# DI_DO.net
KiCad netlist of a schematic drawn in Altium Designer
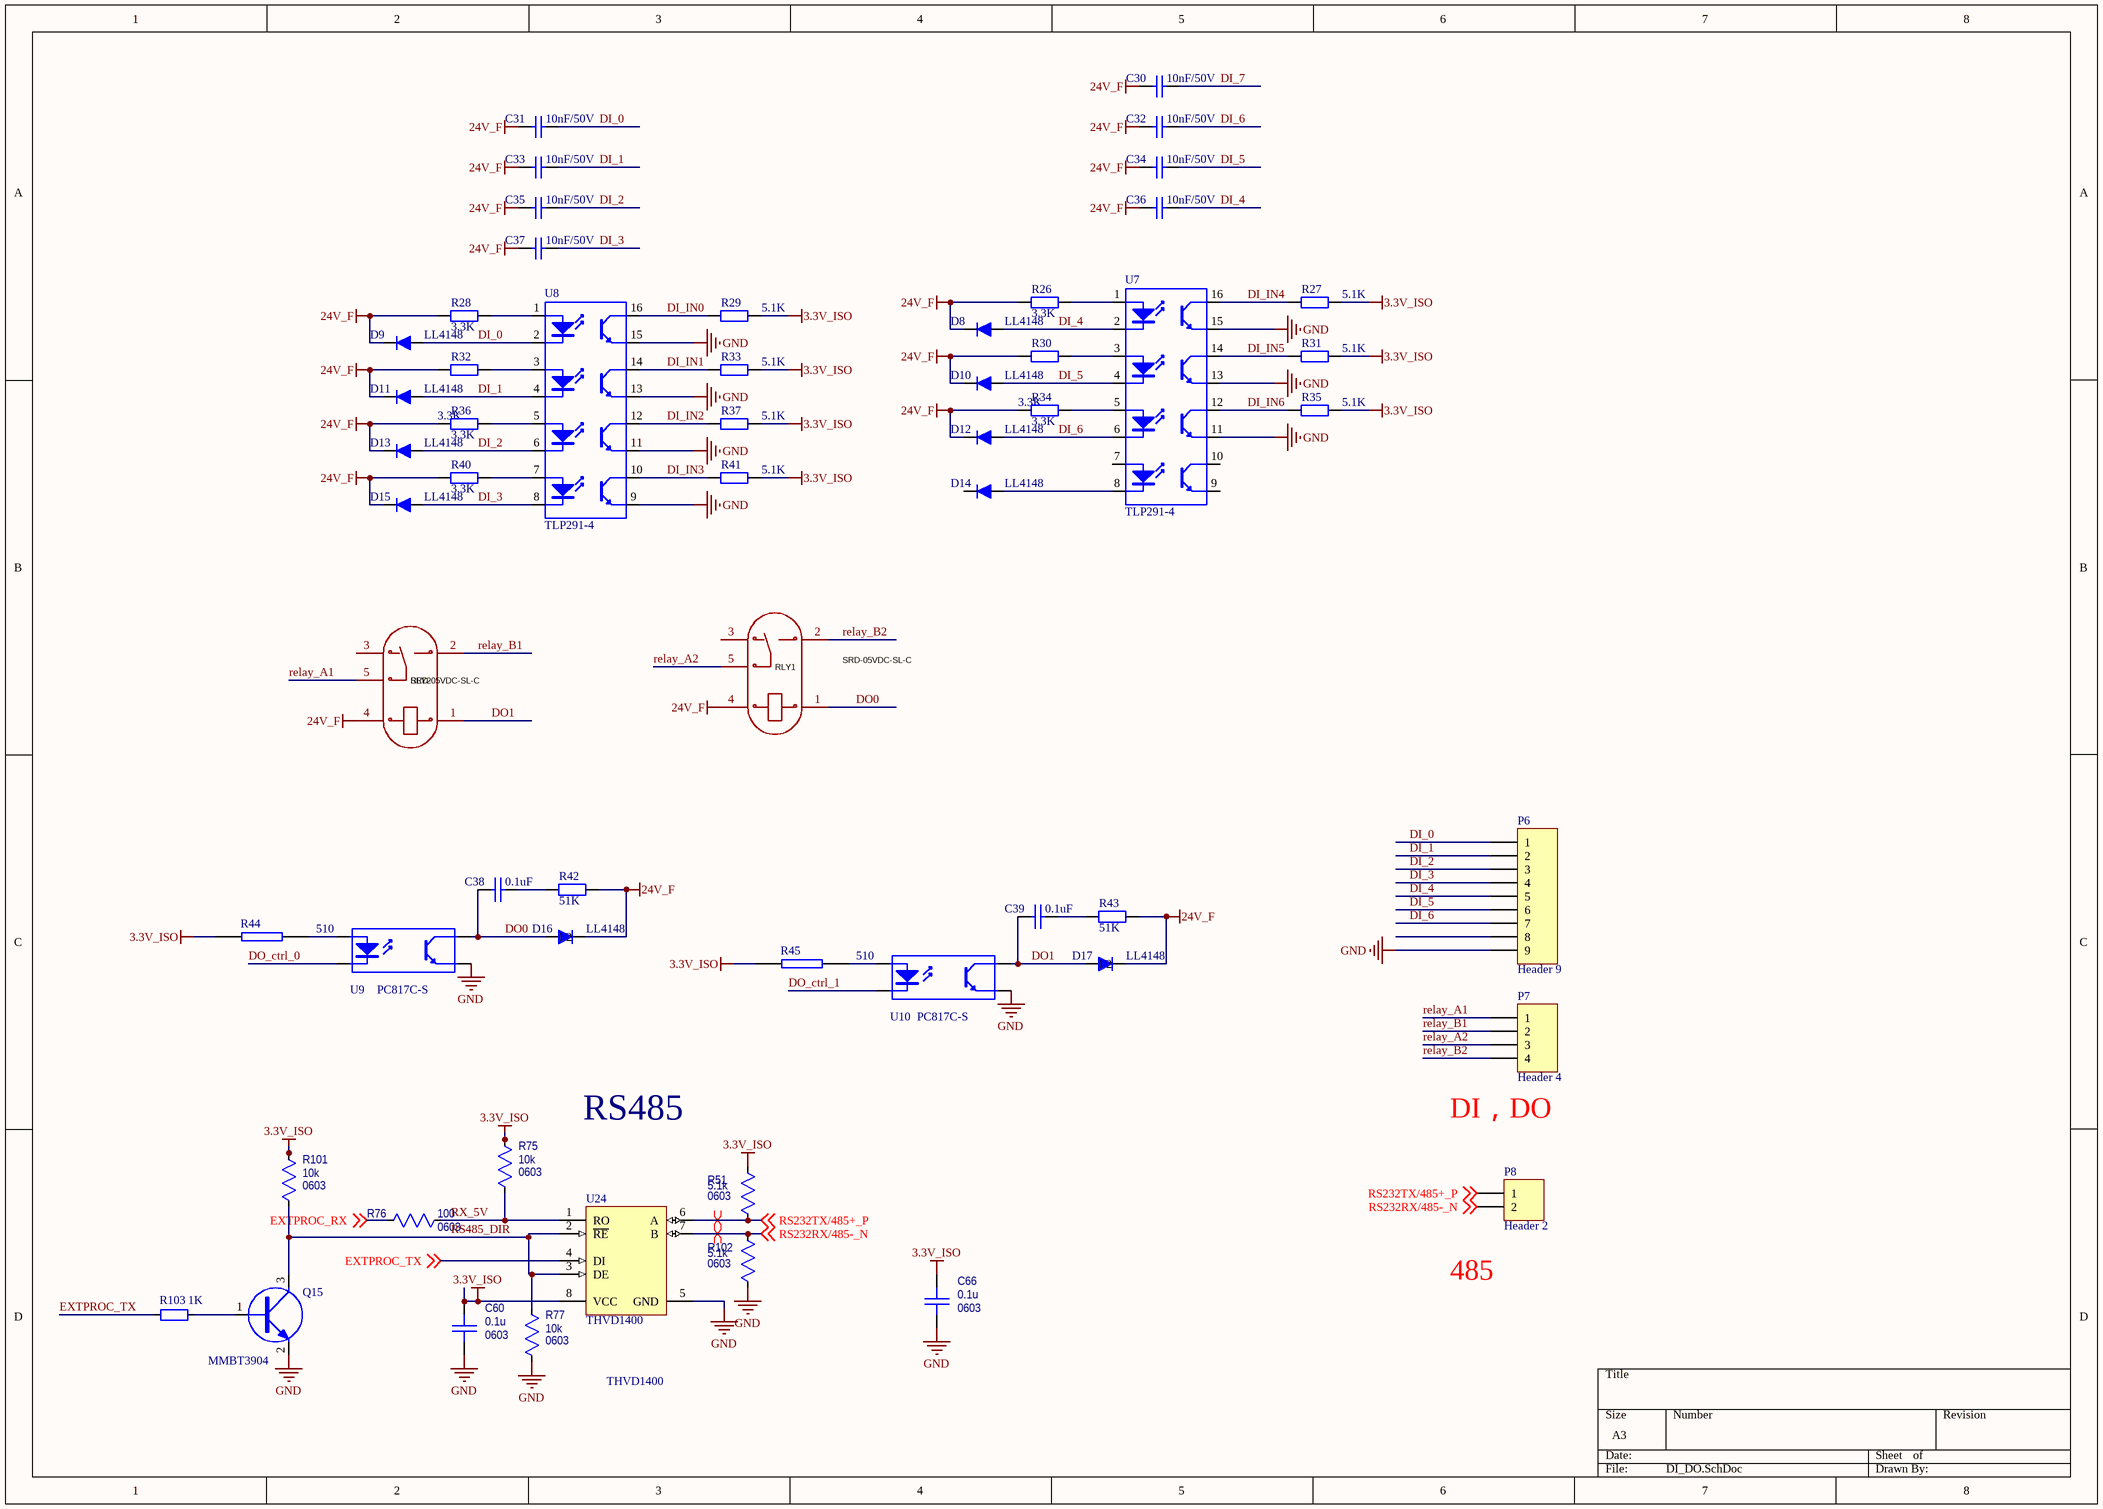
[diagram p0: DI_DO.SchDoc]

(export (version "E")
  (design (tool "Eeschema 10.0.6"))
  (components
    (comp (ref "C30")
      (value "10nF/50V")
      (footprint "0603C")
      (description "Capacitor")
      (fields (field (name "PUBLISHER") "Altium Limited"))
      (libsource (lib "Miscellaneous Devices") (part "Cap"))
    )
    (comp (ref "C31")
      (value "10nF/50V")
      (footprint "0603C")
      (description "Capacitor")
      (fields (field (name "PUBLISHER") "Altium Limited"))
      (libsource (lib "Miscellaneous Devices") (part "Cap"))
    )
    (comp (ref "C32")
      (value "10nF/50V")
      (footprint "0603C")
      (description "Capacitor")
      (fields (field (name "PUBLISHER") "Altium Limited"))
      (libsource (lib "Miscellaneous Devices") (part "Cap"))
    )
    (comp (ref "C33")
      (value "10nF/50V")
      (footprint "0603C")
      (description "Capacitor")
      (fields (field (name "PUBLISHER") "Altium Limited"))
      (libsource (lib "Miscellaneous Devices") (part "Cap"))
    )
    (comp (ref "C34")
      (value "10nF/50V")
      (footprint "0603C")
      (description "Capacitor")
      (fields (field (name "PUBLISHER") "Altium Limited"))
      (libsource (lib "Miscellaneous Devices") (part "Cap"))
    )
    (comp (ref "C35")
      (value "10nF/50V")
      (footprint "0603C")
      (description "Capacitor")
      (fields (field (name "PUBLISHER") "Altium Limited"))
      (libsource (lib "Miscellaneous Devices") (part "Cap"))
    )
    (comp (ref "C36")
      (value "10nF/50V")
      (footprint "0603C")
      (description "Capacitor")
      (fields (field (name "PUBLISHER") "Altium Limited"))
      (libsource (lib "Miscellaneous Devices") (part "Cap"))
    )
    (comp (ref "C37")
      (value "10nF/50V")
      (footprint "0603C")
      (description "Capacitor")
      (fields (field (name "PUBLISHER") "Altium Limited"))
      (libsource (lib "Miscellaneous Devices") (part "Cap"))
    )
    (comp (ref "C38")
      (value "0.1uF")
      (footprint "0603C")
      (description "Capacitor")
      (libsource (lib "*") (part "CAP"))
    )
    (comp (ref "C39")
      (value "0.1uF")
      (footprint "0603C")
      (description "Capacitor")
      (libsource (lib "*") (part "CAP"))
    )
    (comp (ref "C60")
      (value "0.1u")
      (footprint "CAPC1608X092N_0603")
      (description "Capacitor, MLCC")
      (fields
        (field (name "PARTNUMBER") "C0603C104M5RACTU")
        (field (name "TOLERANCE") "[tol]")
        (field (name "PACKAGE") "0603")
      )
      (libsource (lib "Karl") (part "Capacitor_0603"))
    )
    (comp (ref "C66")
      (value "0.1u")
      (footprint "CAPC1608X092N_0603")
      (description "Capacitor, MLCC")
      (fields
        (field (name "PARTNUMBER") "C0603C104M5RACTU")
        (field (name "TOLERANCE") "[tol]")
        (field (name "PACKAGE") "0603")
      )
      (libsource (lib "Karl") (part "Capacitor_0603"))
    )
    (comp (ref "D8")
      (value "LL4148")
      (footprint "DO-213AB/LL34/MiniMELF")
      (description "VISHAY,LL4148,圆柱体MiniMELF100V/2A,ROHS")
      (libsource (lib "Device2018") (part "LL4148"))
    )
    (comp (ref "D9")
      (value "LL4148")
      (footprint "DO-213AB/LL34/MiniMELF")
      (description "VISHAY,LL4148,圆柱体MiniMELF100V/2A,ROHS")
      (libsource (lib "Device2018") (part "LL4148"))
    )
    (comp (ref "D10")
      (value "LL4148")
      (footprint "DO-213AB/LL34/MiniMELF")
      (description "VISHAY,LL4148,圆柱体MiniMELF100V/2A,ROHS")
      (libsource (lib "Device2018") (part "LL4148"))
    )
    (comp (ref "D11")
      (value "LL4148")
      (footprint "DO-213AB/LL34/MiniMELF")
      (description "VISHAY,LL4148,圆柱体MiniMELF100V/2A,ROHS")
      (libsource (lib "Device2018") (part "LL4148"))
    )
    (comp (ref "D12")
      (value "LL4148")
      (footprint "DO-213AB/LL34/MiniMELF")
      (description "VISHAY,LL4148,圆柱体MiniMELF100V/2A,ROHS")
      (libsource (lib "Device2018") (part "LL4148"))
    )
    (comp (ref "D13")
      (value "LL4148")
      (footprint "DO-213AB/LL34/MiniMELF")
      (description "VISHAY,LL4148,圆柱体MiniMELF100V/2A,ROHS")
      (libsource (lib "Device2018") (part "LL4148"))
    )
    (comp (ref "D14")
      (value "LL4148")
      (footprint "DO-213AB/LL34/MiniMELF")
      (description "VISHAY,LL4148,圆柱体MiniMELF100V/2A,ROHS")
      (libsource (lib "Device2018") (part "LL4148"))
    )
    (comp (ref "D15")
      (value "LL4148")
      (footprint "DO-213AB/LL34/MiniMELF")
      (description "VISHAY,LL4148,圆柱体MiniMELF100V/2A,ROHS")
      (libsource (lib "Device2018") (part "LL4148"))
    )
    (comp (ref "D16")
      (value "LL4148")
      (footprint "DO-213AB/LL34/MiniMELF")
      (description "VISHAY,LL4148,圆柱体MiniMELF100V/2A,ROHS")
      (libsource (lib "") (part "LL4148_1"))
    )
    (comp (ref "D17")
      (value "LL4148")
      (footprint "DO-213AB/LL34/MiniMELF")
      (description "VISHAY,LL4148,圆柱体MiniMELF100V/2A,ROHS")
      (libsource (lib "") (part "LL4148_1"))
    )
    (comp (ref "P6")
      (value "Header 9")
      (footprint "HDR1X9")
      (description "Header, 9-Pin")
      (fields (field (name "PUBLISHER") "Altium Limited"))
      (libsource (lib "Miscellaneous Connectors") (part "Header 9"))
    )
    (comp (ref "P7")
      (value "Header 4")
      (footprint "HDR1X4")
      (description "Header, 4-Pin")
      (fields (field (name "PUBLISHER") "Altium Limited"))
      (libsource (lib "Miscellaneous Connectors") (part "Header 4"))
    )
    (comp (ref "P8")
      (value "Header 2")
      (footprint "HDR1X2")
      (description "Header, 2-Pin")
      (fields (field (name "PUBLISHER") "Altium Limited"))
      (libsource (lib "Miscellaneous Connectors") (part "Header 2"))
    )
    (comp (ref "Q15")
      (value "MMBT3904")
      (footprint "SOT23-3")
      (libsource (lib "CenLib") (part "NPN_MMBT3904"))
    )
    (comp (ref "R26") (value "3.3K") (footprint "0603R") (libsource (lib "MQlibrary") (part "Res0805M")))
    (comp (ref "R27") (value "5.1K") (footprint "0603R") (libsource (lib "MQlibrary") (part "Res0805M")))
    (comp (ref "R28") (value "3.3K") (footprint "0603R") (libsource (lib "MQlibrary") (part "Res0805M")))
    (comp (ref "R29") (value "5.1K") (footprint "0603R") (libsource (lib "MQlibrary") (part "Res0805M")))
    (comp (ref "R30") (value "3.3K") (footprint "0603R") (libsource (lib "MQlibrary") (part "Res0805M")))
    (comp (ref "R31") (value "5.1K") (footprint "0603R") (libsource (lib "MQlibrary") (part "Res0805M")))
    (comp (ref "R32") (value "3.3K") (footprint "0603R") (libsource (lib "MQlibrary") (part "Res0805M")))
    (comp (ref "R33") (value "5.1K") (footprint "0603R") (libsource (lib "MQlibrary") (part "Res0805M")))
    (comp (ref "R34") (value "3.3K") (footprint "0603R") (libsource (lib "MQlibrary") (part "Res0805M")))
    (comp (ref "R35") (value "5.1K") (footprint "0603R") (libsource (lib "MQlibrary") (part "Res0805M")))
    (comp (ref "R36") (value "3.3K") (footprint "0603R") (libsource (lib "MQlibrary") (part "Res0805M")))
    (comp (ref "R37") (value "5.1K") (footprint "0603R") (libsource (lib "MQlibrary") (part "Res0805M")))
    (comp (ref "R40") (value "3.3K") (footprint "0603R") (libsource (lib "MQlibrary") (part "Res0805M")))
    (comp (ref "R41") (value "5.1K") (footprint "0603R") (libsource (lib "MQlibrary") (part "Res0805M")))
    (comp (ref "R42") (value "51K") (footprint "0603R") (libsource (lib "") (part "Res0805M_1")))
    (comp (ref "R43") (value "51K") (footprint "0603R") (libsource (lib "") (part "Res0805M_1")))
    (comp (ref "R44") (value "510") (footprint "0603R") (libsource (lib "*") (part "RES2")))
    (comp (ref "R45") (value "510") (footprint "0603R") (libsource (lib "*") (part "RES2")))
    (comp (ref "R51")
      (value "5.1k")
      (footprint "0603r")
      (fields
        (field (name "PARTNUMBER") "RC0603FR-071KL")
        (field (name "TOLERANCE") "tol")
        (field (name "PACKAGE") "0603")
        (field (name "Comment") "10k")
      )
      (libsource (lib "Karl") (part "Resistor_0603"))
    )
    (comp (ref "R75")
      (value "10k")
      (footprint "RESC1608X055N_0603")
      (description "Resistor, Standard")
      (fields
        (field (name "PARTNUMBER") "RC0603FR-0710KL")
        (field (name "TOLERANCE") "tol")
        (field (name "PACKAGE") "0603")
      )
      (libsource (lib "Karl") (part "Resistor_0603"))
    )
    (comp (ref "R76")
      (value "100")
      (footprint "RESC1608X055N_0603")
      (description "Resistor, Standard")
      (fields
        (field (name "PARTNUMBER") "RC0603FR-07100RL")
        (field (name "TOLERANCE") "tol")
        (field (name "PACKAGE") "0603")
      )
      (libsource (lib "Karl") (part "Resistor_0603"))
    )
    (comp (ref "R77")
      (value "10k")
      (footprint "RESC1608X055N_0603")
      (description "Resistor, Standard")
      (fields
        (field (name "PARTNUMBER") "RC0603FR-0710KL")
        (field (name "TOLERANCE") "tol")
        (field (name "PACKAGE") "0603")
      )
      (libsource (lib "Karl") (part "Resistor_0603"))
    )
    (comp (ref "R101")
      (value "10k")
      (footprint "RESC1608X055N_0603")
      (description "Resistor, Standard")
      (fields
        (field (name "PARTNUMBER") "RC0603FR-0710KL")
        (field (name "TOLERANCE") "tol")
        (field (name "PACKAGE") "0603")
      )
      (libsource (lib "Karl") (part "Resistor_0603"))
    )
    (comp (ref "R102")
      (value "5.1k")
      (footprint "0603r")
      (fields
        (field (name "PARTNUMBER") "RC0603FR-071KL")
        (field (name "TOLERANCE") "tol")
        (field (name "PACKAGE") "0603")
        (field (name "Comment") "10k")
      )
      (libsource (lib "Karl") (part "Resistor_0603"))
    )
    (comp (ref "R103") (value "1K") (footprint "0603r") (libsource (lib "RC_M_D_00") (part "RES0603")))
    (comp (ref "RLY1")
      (value "SRD-05VDC-SL-C")
      (footprint "RELAY-TH_SRD-XXVDC-XL-C")
      (fields (field (name "MANUFACTURER") "松乐"))
      (libsource (lib "altium-import") (part "root_0_SRD-05VDC-SL-C_"))
    )
    (comp (ref "RLY2")
      (value "SRD-05VDC-SL-C")
      (footprint "RELAY-TH_SRD-XXVDC-XL-C")
      (fields (field (name "MANUFACTURER") "松乐"))
      (libsource (lib "altium-import") (part "root_0_SRD-05VDC-SL-C_"))
    )
    (comp (ref "U7") (value "TLP291-4") (footprint "SOP16-T") (libsource (lib "DI16") (part "TLP281-4")))
    (comp (ref "U8") (value "TLP291-4") (footprint "SOP16-T") (libsource (lib "DI16") (part "TLP281-4")))
    (comp (ref "U9")
      (value "PC817C-S")
      (footprint "sop4")
      (description "4-Pin Phototransistor Optocoupler")
      (fields (field (name "PUBLISHER") "Altium Limited"))
      (libsource (lib "Miscellaneous Devices") (part "Optoisolator1"))
    )
    (comp (ref "U10")
      (value "PC817C-S")
      (footprint "sop4")
      (description "4-Pin Phototransistor Optocoupler")
      (fields (field (name "PUBLISHER") "Altium Limited"))
      (libsource (lib "Miscellaneous Devices") (part "Optoisolator1"))
    )
    (comp (ref "U24")
      (value "THVD1400")
      (footprint "MAXM-S8+4_M")
      (fields (field (name "PARTNUMBER") "MAX33071EASA+"))
      (libsource (lib "Bogen") (part "MAX33071EASA+"))
    )
  )
  (nets
    (net (code "1") (name "/DI_0") (class "Default")
      (node (ref "C31") (pin "2") (pinfunction "2_2") (pintype "passive"))
      (node (ref "D9") (pin "1") (pinfunction "2_1") (pintype "passive"))
      (node (ref "P6") (pin "1") (pinfunction "1_1") (pintype "passive"))
      (node (ref "U8") (pin "2") (pinfunction "K_2") (pintype "passive"))
    )
    (net (code "2") (name "/DI_1") (class "Default")
      (node (ref "C33") (pin "2") (pinfunction "2_2") (pintype "passive"))
      (node (ref "D11") (pin "1") (pinfunction "2_1") (pintype "passive"))
      (node (ref "P6") (pin "2") (pinfunction "2_2") (pintype "passive"))
      (node (ref "U8") (pin "4") (pinfunction "K_4") (pintype "passive"))
    )
    (net (code "3") (name "/DI_2") (class "Default")
      (node (ref "C35") (pin "2") (pinfunction "2_2") (pintype "passive"))
      (node (ref "D13") (pin "1") (pinfunction "2_1") (pintype "passive"))
      (node (ref "P6") (pin "3") (pinfunction "3_3") (pintype "passive"))
      (node (ref "U8") (pin "6") (pinfunction "K_6") (pintype "passive"))
    )
    (net (code "4") (name "/DI_3") (class "Default")
      (node (ref "C37") (pin "2") (pinfunction "2_2") (pintype "passive"))
      (node (ref "D15") (pin "1") (pinfunction "2_1") (pintype "passive"))
      (node (ref "P6") (pin "4") (pinfunction "4_4") (pintype "passive"))
      (node (ref "U8") (pin "8") (pinfunction "K_8") (pintype "passive"))
    )
    (net (code "5") (name "/DI_4") (class "Default")
      (node (ref "C36") (pin "2") (pinfunction "2_2") (pintype "passive"))
      (node (ref "D8") (pin "1") (pinfunction "2_1") (pintype "passive"))
      (node (ref "P6") (pin "5") (pinfunction "5_5") (pintype "passive"))
      (node (ref "U7") (pin "2") (pinfunction "K_2") (pintype "passive"))
    )
    (net (code "6") (name "/DI_5") (class "Default")
      (node (ref "C34") (pin "2") (pinfunction "2_2") (pintype "passive"))
      (node (ref "D10") (pin "1") (pinfunction "2_1") (pintype "passive"))
      (node (ref "P6") (pin "6") (pinfunction "6_6") (pintype "passive"))
      (node (ref "U7") (pin "4") (pinfunction "K_4") (pintype "passive"))
    )
    (net (code "7") (name "/DI_6") (class "Default")
      (node (ref "C32") (pin "2") (pinfunction "2_2") (pintype "passive"))
      (node (ref "D12") (pin "1") (pinfunction "2_1") (pintype "passive"))
      (node (ref "P6") (pin "7") (pinfunction "7_7") (pintype "passive"))
      (node (ref "U7") (pin "6") (pinfunction "K_6") (pintype "passive"))
    )
    (net (code "8") (name "/DI_7") (class "Default")
      (node (ref "C30") (pin "2") (pinfunction "2_2") (pintype "passive"))
    )
    (net (code "9") (name "/DI_IN0") (class "Default")
      (node (ref "R29") (pin "2") (pinfunction "2_2") (pintype "passive"))
      (node (ref "U8") (pin "16") (pinfunction "C_16") (pintype "passive"))
    )
    (net (code "10") (name "/DI_IN1") (class "Default")
      (node (ref "R33") (pin "2") (pinfunction "2_2") (pintype "passive"))
      (node (ref "U8") (pin "14") (pinfunction "C_14") (pintype "passive"))
    )
    (net (code "11") (name "/DI_IN2") (class "Default")
      (node (ref "R37") (pin "2") (pinfunction "2_2") (pintype "passive"))
      (node (ref "U8") (pin "12") (pinfunction "C_12") (pintype "passive"))
    )
    (net (code "12") (name "/DI_IN3") (class "Default")
      (node (ref "R41") (pin "2") (pinfunction "2_2") (pintype "passive"))
      (node (ref "U8") (pin "10") (pinfunction "C_10") (pintype "passive"))
    )
    (net (code "13") (name "/DI_IN4") (class "Default")
      (node (ref "R27") (pin "2") (pinfunction "2_2") (pintype "passive"))
      (node (ref "U7") (pin "16") (pinfunction "C_16") (pintype "passive"))
    )
    (net (code "14") (name "/DI_IN5") (class "Default")
      (node (ref "R31") (pin "2") (pinfunction "2_2") (pintype "passive"))
      (node (ref "U7") (pin "14") (pinfunction "C_14") (pintype "passive"))
    )
    (net (code "15") (name "/DI_IN6") (class "Default")
      (node (ref "R35") (pin "2") (pinfunction "2_2") (pintype "passive"))
      (node (ref "U7") (pin "12") (pinfunction "C_12") (pintype "passive"))
    )
    (net (code "16") (name "/DO0") (class "Default")
      (node (ref "C38") (pin "1") (pinfunction "1_1") (pintype "passive"))
      (node (ref "D16") (pin "1") (pinfunction "2_1") (pintype "passive"))
      (node (ref "RLY1") (pin "1") (pinfunction "1_1") (pintype "passive"))
      (node (ref "U9") (pin "4") (pinfunction "C_4") (pintype "passive"))
    )
    (net (code "17") (name "/DO1") (class "Default")
      (node (ref "C39") (pin "1") (pinfunction "1_1") (pintype "passive"))
      (node (ref "D17") (pin "1") (pinfunction "2_1") (pintype "passive"))
      (node (ref "RLY2") (pin "1") (pinfunction "1_1") (pintype "passive"))
      (node (ref "U10") (pin "4") (pinfunction "C_4") (pintype "passive"))
    )
    (net (code "18") (name "/DO_ctrl_0") (class "Default")
      (node (ref "U9") (pin "2") (pinfunction "K_2") (pintype "passive"))
    )
    (net (code "19") (name "/DO_ctrl_1") (class "Default")
      (node (ref "U10") (pin "2") (pinfunction "K_2") (pintype "passive"))
    )
    (net (code "20") (name "/RS485_DIR") (class "Default")
      (node (ref "Q15") (pin "3") (pinfunction "C_3") (pintype "passive"))
      (node (ref "R101") (pin "1") (pinfunction "1_1") (pintype "passive"))
      (node (ref "R77") (pin "2") (pinfunction "2_2") (pintype "passive"))
      (node (ref "U24") (pin "2") (pinfunction "~{RE}_2") (pintype "input"))
      (node (ref "U24") (pin "3") (pinfunction "DE_3") (pintype "input"))
    )
    (net (code "21") (name "/RX_5V") (class "Default")
      (node (ref "R75") (pin "1") (pinfunction "1_1") (pintype "passive"))
      (node (ref "R76") (pin "1") (pinfunction "1_1") (pintype "passive"))
      (node (ref "U24") (pin "1") (pinfunction "RO_1") (pintype "tri_state"))
    )
    (net (code "22") (name "/relay_A1") (class "Default")
      (node (ref "P7") (pin "1") (pinfunction "1_1") (pintype "passive"))
      (node (ref "RLY2") (pin "5") (pinfunction "5_5") (pintype "passive"))
    )
    (net (code "23") (name "/relay_A2") (class "Default")
      (node (ref "P7") (pin "3") (pinfunction "3_3") (pintype "passive"))
      (node (ref "RLY1") (pin "5") (pinfunction "5_5") (pintype "passive"))
    )
    (net (code "24") (name "/relay_B1") (class "Default")
      (node (ref "P7") (pin "2") (pinfunction "2_2") (pintype "passive"))
      (node (ref "RLY2") (pin "2") (pinfunction "2_2") (pintype "passive"))
    )
    (net (code "25") (name "/relay_B2") (class "Default")
      (node (ref "P7") (pin "4") (pinfunction "4_4") (pintype "passive"))
      (node (ref "RLY1") (pin "2") (pinfunction "2_2") (pintype "passive"))
    )
    (net (code "26") (name "3.3V_ISO") (class "Default")
      (node (ref "C60") (pin "1") (pinfunction "1_1") (pintype "passive"))
      (node (ref "C66") (pin "1") (pinfunction "1_1") (pintype "passive"))
      (node (ref "R101") (pin "2") (pinfunction "2_2") (pintype "passive"))
      (node (ref "R27") (pin "1") (pinfunction "1_1") (pintype "passive"))
      (node (ref "R29") (pin "1") (pinfunction "1_1") (pintype "passive"))
      (node (ref "R31") (pin "1") (pinfunction "1_1") (pintype "passive"))
      (node (ref "R33") (pin "1") (pinfunction "1_1") (pintype "passive"))
      (node (ref "R35") (pin "1") (pinfunction "1_1") (pintype "passive"))
      (node (ref "R37") (pin "1") (pinfunction "1_1") (pintype "passive"))
      (node (ref "R41") (pin "1") (pinfunction "1_1") (pintype "passive"))
      (node (ref "R44") (pin "2") (pinfunction "2_2") (pintype "passive"))
      (node (ref "R45") (pin "2") (pinfunction "2_2") (pintype "passive"))
      (node (ref "R51") (pin "1") (pinfunction "1_1") (pintype "passive"))
      (node (ref "R75") (pin "2") (pinfunction "2_2") (pintype "passive"))
      (node (ref "U24") (pin "8") (pinfunction "VCC_8") (pintype "power_in"))
    )
    (net (code "27") (name "24V_F") (class "Default")
      (node (ref "C30") (pin "1") (pinfunction "1_1") (pintype "passive"))
      (node (ref "C31") (pin "1") (pinfunction "1_1") (pintype "passive"))
      (node (ref "C32") (pin "1") (pinfunction "1_1") (pintype "passive"))
      (node (ref "C33") (pin "1") (pinfunction "1_1") (pintype "passive"))
      (node (ref "C34") (pin "1") (pinfunction "1_1") (pintype "passive"))
      (node (ref "C35") (pin "1") (pinfunction "1_1") (pintype "passive"))
      (node (ref "C36") (pin "1") (pinfunction "1_1") (pintype "passive"))
      (node (ref "C37") (pin "1") (pinfunction "1_1") (pintype "passive"))
      (node (ref "D10") (pin "2") (pinfunction "1_2") (pintype "passive"))
      (node (ref "D11") (pin "2") (pinfunction "1_2") (pintype "passive"))
      (node (ref "D12") (pin "2") (pinfunction "1_2") (pintype "passive"))
      (node (ref "D13") (pin "2") (pinfunction "1_2") (pintype "passive"))
      (node (ref "D15") (pin "2") (pinfunction "1_2") (pintype "passive"))
      (node (ref "D16") (pin "2") (pinfunction "1_2") (pintype "passive"))
      (node (ref "D17") (pin "2") (pinfunction "1_2") (pintype "passive"))
      (node (ref "D8") (pin "2") (pinfunction "1_2") (pintype "passive"))
      (node (ref "D9") (pin "2") (pinfunction "1_2") (pintype "passive"))
      (node (ref "R26") (pin "2") (pinfunction "2_2") (pintype "passive"))
      (node (ref "R28") (pin "2") (pinfunction "2_2") (pintype "passive"))
      (node (ref "R30") (pin "2") (pinfunction "2_2") (pintype "passive"))
      (node (ref "R32") (pin "2") (pinfunction "2_2") (pintype "passive"))
      (node (ref "R34") (pin "2") (pinfunction "2_2") (pintype "passive"))
      (node (ref "R36") (pin "2") (pinfunction "2_2") (pintype "passive"))
      (node (ref "R40") (pin "2") (pinfunction "2_2") (pintype "passive"))
      (node (ref "R42") (pin "2") (pinfunction "2_2") (pintype "passive"))
      (node (ref "R43") (pin "2") (pinfunction "2_2") (pintype "passive"))
      (node (ref "RLY1") (pin "4") (pinfunction "4_4") (pintype "passive"))
      (node (ref "RLY2") (pin "4") (pinfunction "4_4") (pintype "passive"))
    )
    (net (code "28") (name "EXTPROC_RX") (class "Default")
      (node (ref "R76") (pin "2") (pinfunction "2_2") (pintype "passive"))
    )
    (net (code "29") (name "EXTPROC_TX") (class "Default")
      (node (ref "R103") (pin "1") (pinfunction "1_1") (pintype "passive"))
      (node (ref "U24") (pin "4") (pinfunction "DI_4") (pintype "input"))
    )
    (net (code "30") (name "GND") (class "Default")
      (node (ref "C60") (pin "2") (pinfunction "2_2") (pintype "passive"))
      (node (ref "C66") (pin "2") (pinfunction "2_2") (pintype "passive"))
      (node (ref "P6") (pin "9") (pinfunction "9_9") (pintype "passive"))
      (node (ref "Q15") (pin "2") (pinfunction "E_2") (pintype "passive"))
      (node (ref "R102") (pin "2") (pinfunction "2_2") (pintype "passive"))
      (node (ref "R77") (pin "1") (pinfunction "1_1") (pintype "passive"))
      (node (ref "U10") (pin "3") (pinfunction "E_3") (pintype "passive"))
      (node (ref "U24") (pin "5") (pinfunction "GND_5") (pintype "power_in"))
      (node (ref "U7") (pin "11") (pinfunction "E_11") (pintype "passive"))
      (node (ref "U7") (pin "13") (pinfunction "E_13") (pintype "passive"))
      (node (ref "U7") (pin "15") (pinfunction "E_15") (pintype "passive"))
      (node (ref "U8") (pin "11") (pinfunction "E_11") (pintype "passive"))
      (node (ref "U8") (pin "13") (pinfunction "E_13") (pintype "passive"))
      (node (ref "U8") (pin "15") (pinfunction "E_15") (pintype "passive"))
      (node (ref "U8") (pin "9") (pinfunction "E_9") (pintype "passive"))
      (node (ref "U9") (pin "3") (pinfunction "E_3") (pintype "passive"))
    )
    (net (code "31") (name "Net-(C38-Pad2)") (class "Default")
      (node (ref "C38") (pin "2") (pinfunction "2_2") (pintype "passive"))
      (node (ref "R42") (pin "1") (pinfunction "1_1") (pintype "passive"))
    )
    (net (code "32") (name "Net-(C39-Pad2)") (class "Default")
      (node (ref "C39") (pin "2") (pinfunction "2_2") (pintype "passive"))
      (node (ref "R43") (pin "1") (pinfunction "1_1") (pintype "passive"))
    )
    (net (code "33") (name "Net-(D14-2)") (class "Default")
      (node (ref "D14") (pin "1") (pinfunction "2_1") (pintype "passive"))
      (node (ref "U7") (pin "8") (pinfunction "K_8") (pintype "passive"))
    )
    (net (code "34") (name "Net-(Q15-B)") (class "Default")
      (node (ref "Q15") (pin "1") (pinfunction "B_1") (pintype "passive"))
      (node (ref "R103") (pin "2") (pinfunction "2_2") (pintype "passive"))
    )
    (net (code "35") (name "Net-(R26-Pad1)") (class "Default")
      (node (ref "R26") (pin "1") (pinfunction "1_1") (pintype "passive"))
      (node (ref "U7") (pin "1") (pinfunction "A_1") (pintype "passive"))
    )
    (net (code "36") (name "Net-(R28-Pad1)") (class "Default")
      (node (ref "R28") (pin "1") (pinfunction "1_1") (pintype "passive"))
      (node (ref "U8") (pin "1") (pinfunction "A_1") (pintype "passive"))
    )
    (net (code "37") (name "Net-(R30-Pad1)") (class "Default")
      (node (ref "R30") (pin "1") (pinfunction "1_1") (pintype "passive"))
      (node (ref "U7") (pin "3") (pinfunction "A_3") (pintype "passive"))
    )
    (net (code "38") (name "Net-(R32-Pad1)") (class "Default")
      (node (ref "R32") (pin "1") (pinfunction "1_1") (pintype "passive"))
      (node (ref "U8") (pin "3") (pinfunction "A_3") (pintype "passive"))
    )
    (net (code "39") (name "Net-(R34-Pad1)") (class "Default")
      (node (ref "R34") (pin "1") (pinfunction "1_1") (pintype "passive"))
      (node (ref "U7") (pin "5") (pinfunction "A_5") (pintype "passive"))
    )
    (net (code "40") (name "Net-(R36-Pad1)") (class "Default")
      (node (ref "R36") (pin "1") (pinfunction "1_1") (pintype "passive"))
      (node (ref "U8") (pin "5") (pinfunction "A_5") (pintype "passive"))
    )
    (net (code "41") (name "Net-(R40-Pad1)") (class "Default")
      (node (ref "R40") (pin "1") (pinfunction "1_1") (pintype "passive"))
      (node (ref "U8") (pin "7") (pinfunction "A_7") (pintype "passive"))
    )
    (net (code "42") (name "Net-(U9-A)") (class "Default")
      (node (ref "R44") (pin "1") (pinfunction "1_1") (pintype "passive"))
      (node (ref "U9") (pin "1") (pinfunction "A_1") (pintype "passive"))
    )
    (net (code "43") (name "Net-(U10-A)") (class "Default")
      (node (ref "R45") (pin "1") (pinfunction "1_1") (pintype "passive"))
      (node (ref "U10") (pin "1") (pinfunction "A_1") (pintype "passive"))
    )
    (net (code "44") (name "RS232RX{slash}485-_N") (class "Default")
      (node (ref "P8") (pin "2") (pinfunction "2_2") (pintype "passive"))
      (node (ref "R102") (pin "1") (pinfunction "1_1") (pintype "passive"))
      (node (ref "U24") (pin "7") (pinfunction "B_7") (pintype "bidirectional"))
    )
    (net (code "45") (name "RS232TX{slash}485+_P") (class "Default")
      (node (ref "P8") (pin "1") (pinfunction "1_1") (pintype "passive"))
      (node (ref "R51") (pin "2") (pinfunction "2_2") (pintype "passive"))
      (node (ref "U24") (pin "6") (pinfunction "A_6") (pintype "bidirectional"))
    )
    (net (code "46") (name "unconnected-(D14-1-Pad2)") (class "Default")
      (node (ref "D14") (pin "2") (pinfunction "1_2") (pintype "passive"))
    )
    (net (code "47") (name "unconnected-(P6-Pad8)") (class "Default")
      (node (ref "P6") (pin "8") (pinfunction "8_8") (pintype "passive"))
    )
    (net (code "48") (name "unconnected-(RLY1-Pad3)") (class "Default")
      (node (ref "RLY1") (pin "3") (pinfunction "3_3") (pintype "passive"))
    )
    (net (code "49") (name "unconnected-(RLY2-Pad3)") (class "Default")
      (node (ref "RLY2") (pin "3") (pinfunction "3_3") (pintype "passive"))
    )
    (net (code "50") (name "unconnected-(U7-A-Pad7)") (class "Default")
      (node (ref "U7") (pin "7") (pinfunction "A_7") (pintype "passive"))
    )
    (net (code "51") (name "unconnected-(U7-C-Pad10)") (class "Default")
      (node (ref "U7") (pin "10") (pinfunction "C_10") (pintype "passive"))
    )
    (net (code "52") (name "unconnected-(U7-E-Pad9)") (class "Default")
      (node (ref "U7") (pin "9") (pinfunction "E_9") (pintype "passive"))
    )
  )
)
